# SCH_CableUndefinedMini_Rev2_2024-05-01.net
KiCad netlist of a schematic drawn in EasyEDA
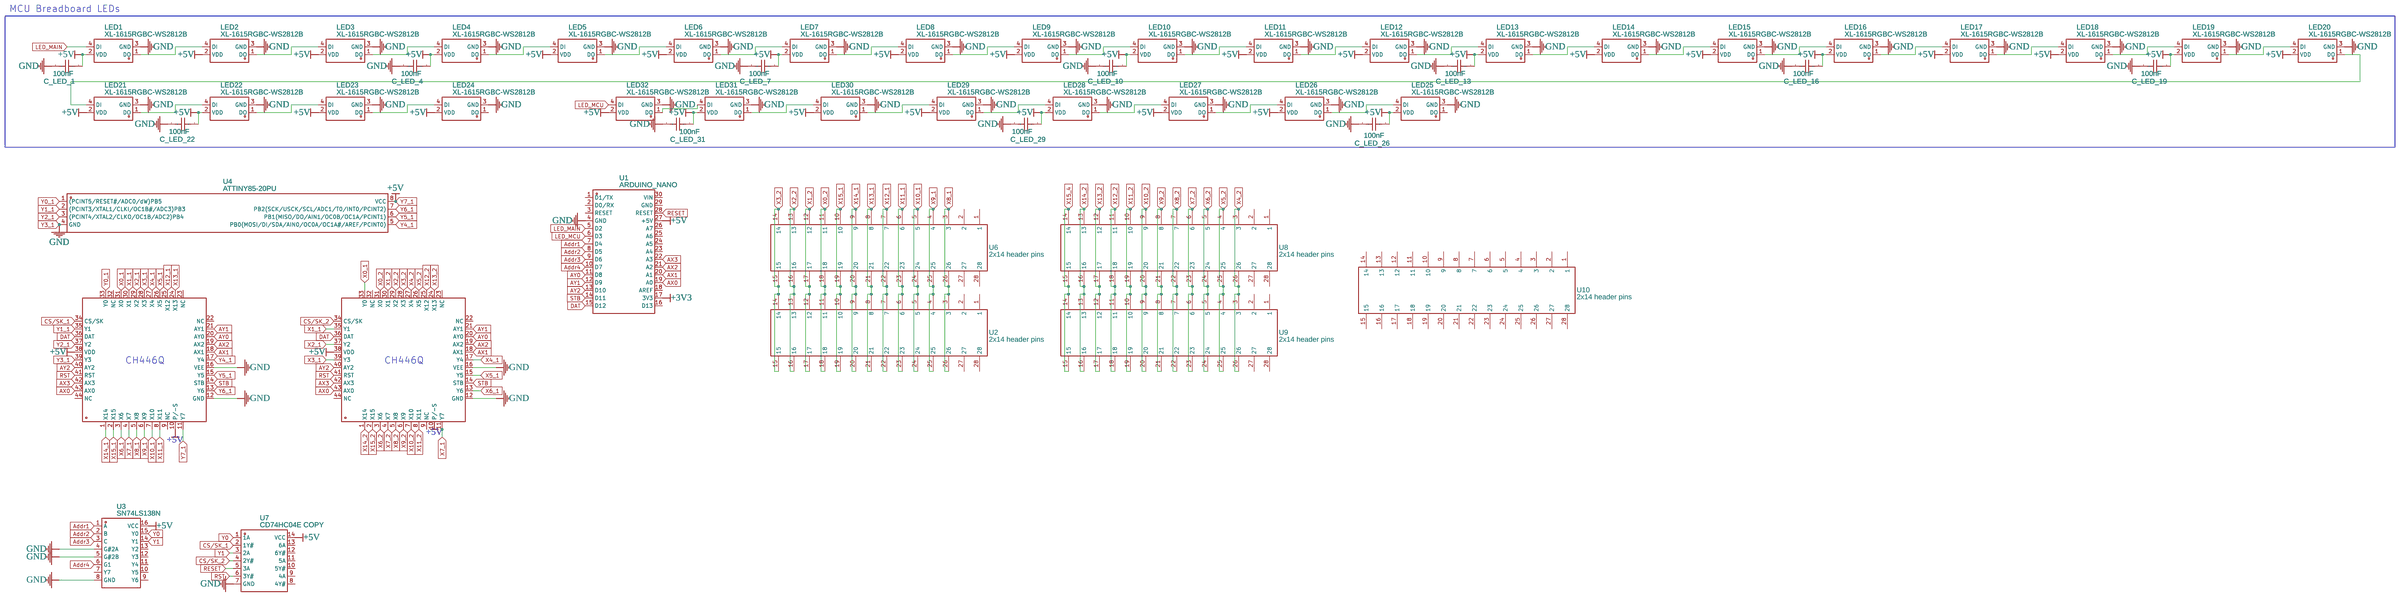
[diagram p0: schematic sheet]

(export (version "E")
  (design (tool "Eeschema 10.0.6"))
  (components
    (comp (ref "C_LED_1")
      (value "100nF")
      (fields (field (name "Manufacturer") "YAGEO(国巨)"))
      (libsource (lib "") (part "AC0402KRX7R9BB104"))
    )
    (comp (ref "C_LED_4")
      (value "100nF")
      (fields (field (name "Manufacturer") "YAGEO(国巨)"))
      (libsource (lib "") (part "AC0402KRX7R9BB104"))
    )
    (comp (ref "C_LED_7")
      (value "100nF")
      (fields (field (name "Manufacturer") "YAGEO(国巨)"))
      (libsource (lib "") (part "AC0402KRX7R9BB104"))
    )
    (comp (ref "C_LED_10")
      (value "100nF")
      (fields (field (name "Manufacturer") "YAGEO(国巨)"))
      (libsource (lib "") (part "AC0402KRX7R9BB104"))
    )
    (comp (ref "C_LED_13")
      (value "100nF")
      (fields (field (name "Manufacturer") "YAGEO(国巨)"))
      (libsource (lib "") (part "AC0402KRX7R9BB104"))
    )
    (comp (ref "C_LED_16")
      (value "100nF")
      (fields (field (name "Manufacturer") "YAGEO(国巨)"))
      (libsource (lib "") (part "AC0402KRX7R9BB104"))
    )
    (comp (ref "C_LED_19")
      (value "100nF")
      (fields (field (name "Manufacturer") "YAGEO(国巨)"))
      (libsource (lib "") (part "AC0402KRX7R9BB104"))
    )
    (comp (ref "C_LED_22")
      (value "100nF")
      (fields (field (name "Manufacturer") "YAGEO(国巨)"))
      (libsource (lib "") (part "AC0402KRX7R9BB104"))
    )
    (comp (ref "C_LED_26")
      (value "100nF")
      (fields (field (name "Manufacturer") "YAGEO(国巨)"))
      (libsource (lib "") (part "AC0402KRX7R9BB104"))
    )
    (comp (ref "C_LED_29")
      (value "100nF")
      (fields (field (name "Manufacturer") "YAGEO(国巨)"))
      (libsource (lib "") (part "AC0402KRX7R9BB104"))
    )
    (comp (ref "C_LED_31")
      (value "100nF")
      (fields (field (name "Manufacturer") "YAGEO(国巨)"))
      (libsource (lib "") (part "AC0402KRX7R9BB104"))
    )
    (comp (ref "LED1")
      (value "XL-1615RGBC-WS2812B")
      (fields (field (name "Manufacturer") "XINGLIGHT(成兴光)"))
      (libsource (lib "") (part "XL-1615RGBC-WS2812B"))
    )
    (comp (ref "LED2")
      (value "XL-1615RGBC-WS2812B")
      (fields (field (name "Manufacturer") "XINGLIGHT(成兴光)"))
      (libsource (lib "") (part "XL-1615RGBC-WS2812B"))
    )
    (comp (ref "LED3")
      (value "XL-1615RGBC-WS2812B")
      (fields (field (name "Manufacturer") "XINGLIGHT(成兴光)"))
      (libsource (lib "") (part "XL-1615RGBC-WS2812B"))
    )
    (comp (ref "LED4")
      (value "XL-1615RGBC-WS2812B")
      (fields (field (name "Manufacturer") "XINGLIGHT(成兴光)"))
      (libsource (lib "") (part "XL-1615RGBC-WS2812B"))
    )
    (comp (ref "LED5")
      (value "XL-1615RGBC-WS2812B")
      (fields (field (name "Manufacturer") "XINGLIGHT(成兴光)"))
      (libsource (lib "") (part "XL-1615RGBC-WS2812B"))
    )
    (comp (ref "LED6")
      (value "XL-1615RGBC-WS2812B")
      (fields (field (name "Manufacturer") "XINGLIGHT(成兴光)"))
      (libsource (lib "") (part "XL-1615RGBC-WS2812B"))
    )
    (comp (ref "LED7")
      (value "XL-1615RGBC-WS2812B")
      (fields (field (name "Manufacturer") "XINGLIGHT(成兴光)"))
      (libsource (lib "") (part "XL-1615RGBC-WS2812B"))
    )
    (comp (ref "LED8")
      (value "XL-1615RGBC-WS2812B")
      (fields (field (name "Manufacturer") "XINGLIGHT(成兴光)"))
      (libsource (lib "") (part "XL-1615RGBC-WS2812B"))
    )
    (comp (ref "LED9")
      (value "XL-1615RGBC-WS2812B")
      (fields (field (name "Manufacturer") "XINGLIGHT(成兴光)"))
      (libsource (lib "") (part "XL-1615RGBC-WS2812B"))
    )
    (comp (ref "LED10")
      (value "XL-1615RGBC-WS2812B")
      (fields (field (name "Manufacturer") "XINGLIGHT(成兴光)"))
      (libsource (lib "") (part "XL-1615RGBC-WS2812B"))
    )
    (comp (ref "LED11")
      (value "XL-1615RGBC-WS2812B")
      (fields (field (name "Manufacturer") "XINGLIGHT(成兴光)"))
      (libsource (lib "") (part "XL-1615RGBC-WS2812B"))
    )
    (comp (ref "LED12")
      (value "XL-1615RGBC-WS2812B")
      (fields (field (name "Manufacturer") "XINGLIGHT(成兴光)"))
      (libsource (lib "") (part "XL-1615RGBC-WS2812B"))
    )
    (comp (ref "LED13")
      (value "XL-1615RGBC-WS2812B")
      (fields (field (name "Manufacturer") "XINGLIGHT(成兴光)"))
      (libsource (lib "") (part "XL-1615RGBC-WS2812B"))
    )
    (comp (ref "LED14")
      (value "XL-1615RGBC-WS2812B")
      (fields (field (name "Manufacturer") "XINGLIGHT(成兴光)"))
      (libsource (lib "") (part "XL-1615RGBC-WS2812B"))
    )
    (comp (ref "LED15")
      (value "XL-1615RGBC-WS2812B")
      (fields (field (name "Manufacturer") "XINGLIGHT(成兴光)"))
      (libsource (lib "") (part "XL-1615RGBC-WS2812B"))
    )
    (comp (ref "LED16")
      (value "XL-1615RGBC-WS2812B")
      (fields (field (name "Manufacturer") "XINGLIGHT(成兴光)"))
      (libsource (lib "") (part "XL-1615RGBC-WS2812B"))
    )
    (comp (ref "LED17")
      (value "XL-1615RGBC-WS2812B")
      (fields (field (name "Manufacturer") "XINGLIGHT(成兴光)"))
      (libsource (lib "") (part "XL-1615RGBC-WS2812B"))
    )
    (comp (ref "LED18")
      (value "XL-1615RGBC-WS2812B")
      (fields (field (name "Manufacturer") "XINGLIGHT(成兴光)"))
      (libsource (lib "") (part "XL-1615RGBC-WS2812B"))
    )
    (comp (ref "LED19")
      (value "XL-1615RGBC-WS2812B")
      (fields (field (name "Manufacturer") "XINGLIGHT(成兴光)"))
      (libsource (lib "") (part "XL-1615RGBC-WS2812B"))
    )
    (comp (ref "LED20")
      (value "XL-1615RGBC-WS2812B")
      (fields (field (name "Manufacturer") "XINGLIGHT(成兴光)"))
      (libsource (lib "") (part "XL-1615RGBC-WS2812B"))
    )
    (comp (ref "LED21")
      (value "XL-1615RGBC-WS2812B")
      (fields (field (name "Manufacturer") "XINGLIGHT(成兴光)"))
      (libsource (lib "") (part "XL-1615RGBC-WS2812B"))
    )
    (comp (ref "LED22")
      (value "XL-1615RGBC-WS2812B")
      (fields (field (name "Manufacturer") "XINGLIGHT(成兴光)"))
      (libsource (lib "") (part "XL-1615RGBC-WS2812B"))
    )
    (comp (ref "LED23")
      (value "XL-1615RGBC-WS2812B")
      (fields (field (name "Manufacturer") "XINGLIGHT(成兴光)"))
      (libsource (lib "") (part "XL-1615RGBC-WS2812B"))
    )
    (comp (ref "LED24")
      (value "XL-1615RGBC-WS2812B")
      (fields (field (name "Manufacturer") "XINGLIGHT(成兴光)"))
      (libsource (lib "") (part "XL-1615RGBC-WS2812B"))
    )
    (comp (ref "LED25")
      (value "XL-1615RGBC-WS2812B")
      (fields (field (name "Manufacturer") "XINGLIGHT(成兴光)"))
      (libsource (lib "") (part "XL-1615RGBC-WS2812B"))
    )
    (comp (ref "LED26")
      (value "XL-1615RGBC-WS2812B")
      (fields (field (name "Manufacturer") "XINGLIGHT(成兴光)"))
      (libsource (lib "") (part "XL-1615RGBC-WS2812B"))
    )
    (comp (ref "LED27")
      (value "XL-1615RGBC-WS2812B")
      (fields (field (name "Manufacturer") "XINGLIGHT(成兴光)"))
      (libsource (lib "") (part "XL-1615RGBC-WS2812B"))
    )
    (comp (ref "LED28")
      (value "XL-1615RGBC-WS2812B")
      (fields (field (name "Manufacturer") "XINGLIGHT(成兴光)"))
      (libsource (lib "") (part "XL-1615RGBC-WS2812B"))
    )
    (comp (ref "LED29")
      (value "XL-1615RGBC-WS2812B")
      (fields (field (name "Manufacturer") "XINGLIGHT(成兴光)"))
      (libsource (lib "") (part "XL-1615RGBC-WS2812B"))
    )
    (comp (ref "LED30")
      (value "XL-1615RGBC-WS2812B")
      (fields (field (name "Manufacturer") "XINGLIGHT(成兴光)"))
      (libsource (lib "") (part "XL-1615RGBC-WS2812B"))
    )
    (comp (ref "LED31")
      (value "XL-1615RGBC-WS2812B")
      (fields (field (name "Manufacturer") "XINGLIGHT(成兴光)"))
      (libsource (lib "") (part "XL-1615RGBC-WS2812B"))
    )
    (comp (ref "LED32")
      (value "XL-1615RGBC-WS2812B")
      (fields (field (name "Manufacturer") "XINGLIGHT(成兴光)"))
      (libsource (lib "") (part "XL-1615RGBC-WS2812B"))
    )
    (comp (ref "M1")
      (value "CH446Q")
      (fields (field (name "Manufacturer") "WCH(南京沁恒)"))
      (libsource (lib "") (part "CH446Q"))
    )
    (comp (ref "M2")
      (value "CH446Q")
      (fields (field (name "Manufacturer") "WCH(南京沁恒)"))
      (libsource (lib "") (part "CH446Q"))
    )
    (comp (ref "U1") (value "ARDUINO_NANO") (libsource (lib "") (part "ARDUINO_NANO")))
    (comp (ref "U2") (value "2x14 header pins") (libsource (lib "") (part "2x14 header pins")))
    (comp (ref "U3")
      (value "SN74LS138N")
      (fields (field (name "Manufacturer") "TI(德州仪器)"))
      (libsource (lib "") (part "SN74LS138N"))
    )
    (comp (ref "U4")
      (value "ATTINY85-20PU")
      (fields (field (name "Manufacturer") "MICROCHIP(美国微芯)"))
      (libsource (lib "") (part "ATTINY85-20PU"))
    )
    (comp (ref "U6") (value "2x14 header pins") (libsource (lib "") (part "2x14 header pins")))
    (comp (ref "U7")
      (value "CD74HC04E COPY")
      (fields
        (field (name "Manufacturer Part") "CD74HC04E")
        (field (name "Manufacturer") "Texas Instruments")
      )
      (libsource (lib "") (part "CD74HC04E COPY"))
    )
    (comp (ref "U8") (value "2x14 header pins") (libsource (lib "") (part "2x14 header pins")))
    (comp (ref "U9") (value "2x14 header pins") (libsource (lib "") (part "2x14 header pins")))
    (comp (ref "U10") (value "2x14 header pins") (libsource (lib "") (part "2x14 header pins")))
  )
  (nets
    (net (code "1") (name "+3V3") (class "Default")
      (node (ref "U1") (pin "17") (pinfunction "3V3_17") (pintype "unspecified"))
    )
    (net (code "2") (name "AX0") (class "Default")
      (node (ref "M1") (pin "43") (pinfunction "AX0_43") (pintype "unspecified"))
      (node (ref "M2") (pin "43") (pinfunction "AX0_43") (pintype "unspecified"))
      (node (ref "U1") (pin "19") (pinfunction "A0_19") (pintype "unspecified"))
    )
    (net (code "3") (name "AX1") (class "Default")
      (node (ref "M1") (pin "18") (pinfunction "AX1_18") (pintype "unspecified"))
      (node (ref "M2") (pin "18") (pinfunction "AX1_18") (pintype "unspecified"))
      (node (ref "U1") (pin "20") (pinfunction "A1_20") (pintype "unspecified"))
    )
    (net (code "4") (name "AX2") (class "Default")
      (node (ref "M1") (pin "19") (pinfunction "AX2_19") (pintype "unspecified"))
      (node (ref "M2") (pin "19") (pinfunction "AX2_19") (pintype "unspecified"))
      (node (ref "U1") (pin "21") (pinfunction "A2_21") (pintype "unspecified"))
    )
    (net (code "5") (name "AX3") (class "Default")
      (node (ref "M1") (pin "42") (pinfunction "AX3_42") (pintype "unspecified"))
      (node (ref "M2") (pin "42") (pinfunction "AX3_42") (pintype "unspecified"))
      (node (ref "U1") (pin "22") (pinfunction "A3_22") (pintype "unspecified"))
    )
    (net (code "6") (name "AY0") (class "Default")
      (node (ref "M1") (pin "20") (pinfunction "AY0_20") (pintype "unspecified"))
      (node (ref "M2") (pin "20") (pinfunction "AY0_20") (pintype "unspecified"))
      (node (ref "U1") (pin "11") (pinfunction "D8_11") (pintype "unspecified"))
    )
    (net (code "7") (name "AY1") (class "Default")
      (node (ref "M1") (pin "21") (pinfunction "AY1_21") (pintype "unspecified"))
      (node (ref "M2") (pin "21") (pinfunction "AY1_21") (pintype "unspecified"))
      (node (ref "U1") (pin "12") (pinfunction "D9_12") (pintype "unspecified"))
    )
    (net (code "8") (name "AY2") (class "Default")
      (node (ref "M1") (pin "40") (pinfunction "AY2_40") (pintype "unspecified"))
      (node (ref "M2") (pin "40") (pinfunction "AY2_40") (pintype "unspecified"))
      (node (ref "U1") (pin "13") (pinfunction "D10_13") (pintype "unspecified"))
    )
    (net (code "9") (name "Addr1") (class "Default")
      (node (ref "U1") (pin "7") (pinfunction "D4_7") (pintype "unspecified"))
      (node (ref "U3") (pin "1") (pinfunction "A_1") (pintype "unspecified"))
    )
    (net (code "10") (name "Addr2") (class "Default")
      (node (ref "U1") (pin "8") (pinfunction "D5_8") (pintype "unspecified"))
      (node (ref "U3") (pin "2") (pinfunction "B_2") (pintype "unspecified"))
    )
    (net (code "11") (name "Addr3") (class "Default")
      (node (ref "U1") (pin "9") (pinfunction "D6_9") (pintype "unspecified"))
      (node (ref "U3") (pin "3") (pinfunction "C_3") (pintype "unspecified"))
    )
    (net (code "12") (name "Addr4") (class "Default")
      (node (ref "U1") (pin "10") (pinfunction "D7_10") (pintype "unspecified"))
      (node (ref "U3") (pin "6") (pinfunction "G1_6") (pintype "unspecified"))
    )
    (net (code "13") (name "CS{slash}SK_1") (class "Default")
      (node (ref "M1") (pin "34") (pinfunction "CS/SK_34") (pintype "unspecified"))
      (node (ref "U7") (pin "2") (pinfunction "1Y#_2") (pintype "unspecified"))
    )
    (net (code "14") (name "CS{slash}SK_2") (class "Default")
      (node (ref "M2") (pin "34") (pinfunction "CS/SK_34") (pintype "unspecified"))
      (node (ref "U7") (pin "4") (pinfunction "2Y#_4") (pintype "unspecified"))
    )
    (net (code "15") (name "DAT") (class "Default")
      (node (ref "M1") (pin "36") (pinfunction "DAT_36") (pintype "unspecified"))
      (node (ref "M2") (pin "36") (pinfunction "DAT_36") (pintype "unspecified"))
      (node (ref "U1") (pin "15") (pinfunction "D12_15") (pintype "unspecified"))
    )
    (net (code "16") (name "LED_MAIN") (class "Default")
      (node (ref "LED1") (pin "4") (pinfunction "DI_4") (pintype "unspecified"))
      (node (ref "U1") (pin "5") (pinfunction "D2_5") (pintype "unspecified"))
    )
    (net (code "17") (name "LED_MCU") (class "Default")
      (node (ref "LED32") (pin "4") (pinfunction "DI_4") (pintype "unspecified"))
      (node (ref "U1") (pin "6") (pinfunction "D3_6") (pintype "unspecified"))
    )
    (net (code "18") (name "Net-(LED1-DO)") (class "Default")
      (node (ref "LED1") (pin "1") (pinfunction "DO_1") (pintype "unspecified"))
      (node (ref "LED2") (pin "4") (pinfunction "DI_4") (pintype "unspecified"))
    )
    (net (code "19") (name "Net-(LED2-DO)") (class "Default")
      (node (ref "LED2") (pin "1") (pinfunction "DO_1") (pintype "unspecified"))
      (node (ref "LED3") (pin "4") (pinfunction "DI_4") (pintype "unspecified"))
    )
    (net (code "20") (name "Net-(LED3-DO)") (class "Default")
      (node (ref "LED3") (pin "1") (pinfunction "DO_1") (pintype "unspecified"))
      (node (ref "LED4") (pin "4") (pinfunction "DI_4") (pintype "unspecified"))
    )
    (net (code "21") (name "Net-(LED4-DO)") (class "Default")
      (node (ref "LED4") (pin "1") (pinfunction "DO_1") (pintype "unspecified"))
      (node (ref "LED5") (pin "4") (pinfunction "DI_4") (pintype "unspecified"))
    )
    (net (code "22") (name "Net-(LED5-DO)") (class "Default")
      (node (ref "LED5") (pin "1") (pinfunction "DO_1") (pintype "unspecified"))
      (node (ref "LED6") (pin "4") (pinfunction "DI_4") (pintype "unspecified"))
    )
    (net (code "23") (name "Net-(LED6-DO)") (class "Default")
      (node (ref "LED6") (pin "1") (pinfunction "DO_1") (pintype "unspecified"))
      (node (ref "LED7") (pin "4") (pinfunction "DI_4") (pintype "unspecified"))
    )
    (net (code "24") (name "Net-(LED7-DO)") (class "Default")
      (node (ref "LED7") (pin "1") (pinfunction "DO_1") (pintype "unspecified"))
      (node (ref "LED8") (pin "4") (pinfunction "DI_4") (pintype "unspecified"))
    )
    (net (code "25") (name "Net-(LED8-DO)") (class "Default")
      (node (ref "LED8") (pin "1") (pinfunction "DO_1") (pintype "unspecified"))
      (node (ref "LED9") (pin "4") (pinfunction "DI_4") (pintype "unspecified"))
    )
    (net (code "26") (name "Net-(LED10-DI)") (class "Default")
      (node (ref "LED10") (pin "4") (pinfunction "DI_4") (pintype "unspecified"))
      (node (ref "LED9") (pin "1") (pinfunction "DO_1") (pintype "unspecified"))
    )
    (net (code "27") (name "Net-(LED10-DO)") (class "Default")
      (node (ref "LED10") (pin "1") (pinfunction "DO_1") (pintype "unspecified"))
      (node (ref "LED11") (pin "4") (pinfunction "DI_4") (pintype "unspecified"))
    )
    (net (code "28") (name "Net-(LED11-DO)") (class "Default")
      (node (ref "LED11") (pin "1") (pinfunction "DO_1") (pintype "unspecified"))
      (node (ref "LED12") (pin "4") (pinfunction "DI_4") (pintype "unspecified"))
    )
    (net (code "29") (name "Net-(LED12-DO)") (class "Default")
      (node (ref "LED12") (pin "1") (pinfunction "DO_1") (pintype "unspecified"))
      (node (ref "LED13") (pin "4") (pinfunction "DI_4") (pintype "unspecified"))
    )
    (net (code "30") (name "Net-(LED13-DO)") (class "Default")
      (node (ref "LED13") (pin "1") (pinfunction "DO_1") (pintype "unspecified"))
      (node (ref "LED14") (pin "4") (pinfunction "DI_4") (pintype "unspecified"))
    )
    (net (code "31") (name "Net-(LED14-DO)") (class "Default")
      (node (ref "LED14") (pin "1") (pinfunction "DO_1") (pintype "unspecified"))
      (node (ref "LED15") (pin "4") (pinfunction "DI_4") (pintype "unspecified"))
    )
    (net (code "32") (name "Net-(LED15-DO)") (class "Default")
      (node (ref "LED15") (pin "1") (pinfunction "DO_1") (pintype "unspecified"))
      (node (ref "LED16") (pin "4") (pinfunction "DI_4") (pintype "unspecified"))
    )
    (net (code "33") (name "Net-(LED16-DO)") (class "Default")
      (node (ref "LED16") (pin "1") (pinfunction "DO_1") (pintype "unspecified"))
      (node (ref "LED17") (pin "4") (pinfunction "DI_4") (pintype "unspecified"))
    )
    (net (code "34") (name "Net-(LED17-DO)") (class "Default")
      (node (ref "LED17") (pin "1") (pinfunction "DO_1") (pintype "unspecified"))
      (node (ref "LED18") (pin "4") (pinfunction "DI_4") (pintype "unspecified"))
    )
    (net (code "35") (name "Net-(LED18-DO)") (class "Default")
      (node (ref "LED18") (pin "1") (pinfunction "DO_1") (pintype "unspecified"))
      (node (ref "LED19") (pin "4") (pinfunction "DI_4") (pintype "unspecified"))
    )
    (net (code "36") (name "Net-(LED19-DO)") (class "Default")
      (node (ref "LED19") (pin "1") (pinfunction "DO_1") (pintype "unspecified"))
      (node (ref "LED20") (pin "4") (pinfunction "DI_4") (pintype "unspecified"))
    )
    (net (code "37") (name "Net-(LED20-DO)") (class "Default")
      (node (ref "LED20") (pin "1") (pinfunction "DO_1") (pintype "unspecified"))
      (node (ref "LED21") (pin "4") (pinfunction "DI_4") (pintype "unspecified"))
    )
    (net (code "38") (name "Net-(LED21-DO)") (class "Default")
      (node (ref "LED21") (pin "1") (pinfunction "DO_1") (pintype "unspecified"))
      (node (ref "LED22") (pin "4") (pinfunction "DI_4") (pintype "unspecified"))
    )
    (net (code "39") (name "Net-(LED22-DO)") (class "Default")
      (node (ref "LED22") (pin "1") (pinfunction "DO_1") (pintype "unspecified"))
      (node (ref "LED23") (pin "4") (pinfunction "DI_4") (pintype "unspecified"))
    )
    (net (code "40") (name "Net-(LED23-DO)") (class "Default")
      (node (ref "LED23") (pin "1") (pinfunction "DO_1") (pintype "unspecified"))
      (node (ref "LED24") (pin "4") (pinfunction "DI_4") (pintype "unspecified"))
    )
    (net (code "41") (name "Net-(LED25-DI)") (class "Default")
      (node (ref "LED25") (pin "4") (pinfunction "DI_4") (pintype "unspecified"))
      (node (ref "LED26") (pin "1") (pinfunction "DO_1") (pintype "unspecified"))
    )
    (net (code "42") (name "Net-(LED26-DI)") (class "Default")
      (node (ref "LED26") (pin "4") (pinfunction "DI_4") (pintype "unspecified"))
      (node (ref "LED27") (pin "1") (pinfunction "DO_1") (pintype "unspecified"))
    )
    (net (code "43") (name "Net-(LED27-DI)") (class "Default")
      (node (ref "LED27") (pin "4") (pinfunction "DI_4") (pintype "unspecified"))
      (node (ref "LED28") (pin "1") (pinfunction "DO_1") (pintype "unspecified"))
    )
    (net (code "44") (name "Net-(LED28-DI)") (class "Default")
      (node (ref "LED28") (pin "4") (pinfunction "DI_4") (pintype "unspecified"))
      (node (ref "LED29") (pin "1") (pinfunction "DO_1") (pintype "unspecified"))
    )
    (net (code "45") (name "Net-(LED29-DI)") (class "Default")
      (node (ref "LED29") (pin "4") (pinfunction "DI_4") (pintype "unspecified"))
      (node (ref "LED30") (pin "1") (pinfunction "DO_1") (pintype "unspecified"))
    )
    (net (code "46") (name "Net-(LED30-DI)") (class "Default")
      (node (ref "LED30") (pin "4") (pinfunction "DI_4") (pintype "unspecified"))
      (node (ref "LED31") (pin "1") (pinfunction "DO_1") (pintype "unspecified"))
    )
    (net (code "47") (name "Net-(LED31-DI)") (class "Default")
      (node (ref "LED31") (pin "4") (pinfunction "DI_4") (pintype "unspecified"))
      (node (ref "LED32") (pin "1") (pinfunction "DO_1") (pintype "unspecified"))
    )
    (net (code "48") (name "RESET") (class "Default")
      (node (ref "U1") (pin "28") (pinfunction "RESET_28") (pintype "unspecified"))
      (node (ref "U7") (pin "5") (pinfunction "3A_5") (pintype "unspecified"))
    )
    (net (code "49") (name "RST") (class "Default")
      (node (ref "M1") (pin "41") (pinfunction "RST_41") (pintype "unspecified"))
      (node (ref "M2") (pin "41") (pinfunction "RST_41") (pintype "unspecified"))
      (node (ref "U7") (pin "6") (pinfunction "3Y#_6") (pintype "unspecified"))
    )
    (net (code "50") (name "STB") (class "Default")
      (node (ref "M1") (pin "14") (pinfunction "STB_14") (pintype "unspecified"))
      (node (ref "M2") (pin "14") (pinfunction "STB_14") (pintype "unspecified"))
      (node (ref "U1") (pin "14") (pinfunction "D11_14") (pintype "unspecified"))
    )
    (net (code "51") (name "X0_1") (class "Default")
      (node (ref "M1") (pin "31") (pinfunction "X0_31") (pintype "unspecified"))
      (node (ref "M2") (pin "33") (pinfunction "Y0_33") (pintype "unspecified"))
    )
    (net (code "52") (name "X0_2") (class "Default")
      (node (ref "M2") (pin "31") (pinfunction "X0_31") (pintype "unspecified"))
      (node (ref "U2") (pin "11") (pinfunction "11_11") (pintype "unspecified"))
      (node (ref "U2") (pin "18") (pinfunction "18_18") (pintype "unspecified"))
      (node (ref "U6") (pin "11") (pinfunction "11_11") (pintype "unspecified"))
      (node (ref "U6") (pin "18") (pinfunction "18_18") (pintype "unspecified"))
    )
    (net (code "53") (name "X1_1") (class "Default")
      (node (ref "M1") (pin "30") (pinfunction "X1_30") (pintype "unspecified"))
      (node (ref "M2") (pin "35") (pinfunction "Y1_35") (pintype "unspecified"))
    )
    (net (code "54") (name "X1_2") (class "Default")
      (node (ref "M2") (pin "30") (pinfunction "X1_30") (pintype "unspecified"))
      (node (ref "U2") (pin "12") (pinfunction "12_12") (pintype "unspecified"))
      (node (ref "U2") (pin "17") (pinfunction "17_17") (pintype "unspecified"))
      (node (ref "U6") (pin "12") (pinfunction "12_12") (pintype "unspecified"))
      (node (ref "U6") (pin "17") (pinfunction "17_17") (pintype "unspecified"))
    )
    (net (code "55") (name "X2_1") (class "Default")
      (node (ref "M1") (pin "29") (pinfunction "X2_29") (pintype "unspecified"))
      (node (ref "M2") (pin "37") (pinfunction "Y2_37") (pintype "unspecified"))
    )
    (net (code "56") (name "X2_2") (class "Default")
      (node (ref "M2") (pin "29") (pinfunction "X2_29") (pintype "unspecified"))
      (node (ref "U2") (pin "13") (pinfunction "13_13") (pintype "unspecified"))
      (node (ref "U2") (pin "16") (pinfunction "16_16") (pintype "unspecified"))
      (node (ref "U6") (pin "13") (pinfunction "13_13") (pintype "unspecified"))
      (node (ref "U6") (pin "16") (pinfunction "16_16") (pintype "unspecified"))
    )
    (net (code "57") (name "X3_1") (class "Default")
      (node (ref "M1") (pin "28") (pinfunction "X3_28") (pintype "unspecified"))
      (node (ref "M2") (pin "39") (pinfunction "Y3_39") (pintype "unspecified"))
    )
    (net (code "58") (name "X3_2") (class "Default")
      (node (ref "M2") (pin "28") (pinfunction "X3_28") (pintype "unspecified"))
      (node (ref "U2") (pin "14") (pinfunction "14_14") (pintype "unspecified"))
      (node (ref "U2") (pin "15") (pinfunction "15_15") (pintype "unspecified"))
      (node (ref "U6") (pin "14") (pinfunction "14_14") (pintype "unspecified"))
      (node (ref "U6") (pin "15") (pinfunction "15_15") (pintype "unspecified"))
    )
    (net (code "59") (name "X4_1") (class "Default")
      (node (ref "M1") (pin "27") (pinfunction "X4_27") (pintype "unspecified"))
      (node (ref "M2") (pin "17") (pinfunction "Y4_17") (pintype "unspecified"))
    )
    (net (code "60") (name "X4_2") (class "Default")
      (node (ref "M2") (pin "27") (pinfunction "X4_27") (pintype "unspecified"))
      (node (ref "U8") (pin "26") (pinfunction "26_26") (pintype "unspecified"))
      (node (ref "U8") (pin "3") (pinfunction "3_3") (pintype "unspecified"))
      (node (ref "U9") (pin "26") (pinfunction "26_26") (pintype "unspecified"))
      (node (ref "U9") (pin "3") (pinfunction "3_3") (pintype "unspecified"))
    )
    (net (code "61") (name "X5_1") (class "Default")
      (node (ref "M1") (pin "26") (pinfunction "X5_26") (pintype "unspecified"))
      (node (ref "M2") (pin "15") (pinfunction "Y5_15") (pintype "unspecified"))
    )
    (net (code "62") (name "X5_2") (class "Default")
      (node (ref "M2") (pin "26") (pinfunction "X5_26") (pintype "unspecified"))
      (node (ref "U8") (pin "25") (pinfunction "25_25") (pintype "unspecified"))
      (node (ref "U8") (pin "4") (pinfunction "4_4") (pintype "unspecified"))
      (node (ref "U9") (pin "25") (pinfunction "25_25") (pintype "unspecified"))
      (node (ref "U9") (pin "4") (pinfunction "4_4") (pintype "unspecified"))
    )
    (net (code "63") (name "X6_1") (class "Default")
      (node (ref "M1") (pin "3") (pinfunction "X6_3") (pintype "unspecified"))
      (node (ref "M2") (pin "13") (pinfunction "Y6_13") (pintype "unspecified"))
    )
    (net (code "64") (name "X6_2") (class "Default")
      (node (ref "M2") (pin "3") (pinfunction "X6_3") (pintype "unspecified"))
      (node (ref "U8") (pin "24") (pinfunction "24_24") (pintype "unspecified"))
      (node (ref "U8") (pin "5") (pinfunction "5_5") (pintype "unspecified"))
      (node (ref "U9") (pin "24") (pinfunction "24_24") (pintype "unspecified"))
      (node (ref "U9") (pin "5") (pinfunction "5_5") (pintype "unspecified"))
    )
    (net (code "65") (name "X7_1") (class "Default")
      (node (ref "M1") (pin "4") (pinfunction "X7_4") (pintype "unspecified"))
      (node (ref "M2") (pin "11") (pinfunction "Y7_11") (pintype "unspecified"))
    )
    (net (code "66") (name "X7_2") (class "Default")
      (node (ref "M2") (pin "4") (pinfunction "X7_4") (pintype "unspecified"))
      (node (ref "U8") (pin "23") (pinfunction "23_23") (pintype "unspecified"))
      (node (ref "U8") (pin "6") (pinfunction "6_6") (pintype "unspecified"))
      (node (ref "U9") (pin "23") (pinfunction "23_23") (pintype "unspecified"))
      (node (ref "U9") (pin "6") (pinfunction "6_6") (pintype "unspecified"))
    )
    (net (code "67") (name "X8_1") (class "Default")
      (node (ref "M1") (pin "5") (pinfunction "X8_5") (pintype "unspecified"))
      (node (ref "U2") (pin "26") (pinfunction "26_26") (pintype "unspecified"))
      (node (ref "U2") (pin "3") (pinfunction "3_3") (pintype "unspecified"))
      (node (ref "U6") (pin "26") (pinfunction "26_26") (pintype "unspecified"))
      (node (ref "U6") (pin "3") (pinfunction "3_3") (pintype "unspecified"))
    )
    (net (code "68") (name "X8_2") (class "Default")
      (node (ref "M2") (pin "5") (pinfunction "X8_5") (pintype "unspecified"))
      (node (ref "U8") (pin "22") (pinfunction "22_22") (pintype "unspecified"))
      (node (ref "U8") (pin "7") (pinfunction "7_7") (pintype "unspecified"))
      (node (ref "U9") (pin "22") (pinfunction "22_22") (pintype "unspecified"))
      (node (ref "U9") (pin "7") (pinfunction "7_7") (pintype "unspecified"))
    )
    (net (code "69") (name "X9_1") (class "Default")
      (node (ref "M1") (pin "6") (pinfunction "X9_6") (pintype "unspecified"))
      (node (ref "U2") (pin "25") (pinfunction "25_25") (pintype "unspecified"))
      (node (ref "U2") (pin "4") (pinfunction "4_4") (pintype "unspecified"))
      (node (ref "U6") (pin "25") (pinfunction "25_25") (pintype "unspecified"))
      (node (ref "U6") (pin "4") (pinfunction "4_4") (pintype "unspecified"))
    )
    (net (code "70") (name "X9_2") (class "Default")
      (node (ref "M2") (pin "6") (pinfunction "X9_6") (pintype "unspecified"))
      (node (ref "U8") (pin "21") (pinfunction "21_21") (pintype "unspecified"))
      (node (ref "U8") (pin "8") (pinfunction "8_8") (pintype "unspecified"))
      (node (ref "U9") (pin "21") (pinfunction "21_21") (pintype "unspecified"))
      (node (ref "U9") (pin "8") (pinfunction "8_8") (pintype "unspecified"))
    )
    (net (code "71") (name "X10_1") (class "Default")
      (node (ref "M1") (pin "7") (pinfunction "X10_7") (pintype "unspecified"))
      (node (ref "U2") (pin "24") (pinfunction "24_24") (pintype "unspecified"))
      (node (ref "U2") (pin "5") (pinfunction "5_5") (pintype "unspecified"))
      (node (ref "U6") (pin "24") (pinfunction "24_24") (pintype "unspecified"))
      (node (ref "U6") (pin "5") (pinfunction "5_5") (pintype "unspecified"))
    )
    (net (code "72") (name "X10_2") (class "Default")
      (node (ref "M2") (pin "7") (pinfunction "X10_7") (pintype "unspecified"))
      (node (ref "U8") (pin "20") (pinfunction "20_20") (pintype "unspecified"))
      (node (ref "U8") (pin "9") (pinfunction "9_9") (pintype "unspecified"))
      (node (ref "U9") (pin "20") (pinfunction "20_20") (pintype "unspecified"))
      (node (ref "U9") (pin "9") (pinfunction "9_9") (pintype "unspecified"))
    )
    (net (code "73") (name "X11_1") (class "Default")
      (node (ref "M1") (pin "8") (pinfunction "X11_8") (pintype "unspecified"))
      (node (ref "U2") (pin "23") (pinfunction "23_23") (pintype "unspecified"))
      (node (ref "U2") (pin "6") (pinfunction "6_6") (pintype "unspecified"))
      (node (ref "U6") (pin "23") (pinfunction "23_23") (pintype "unspecified"))
      (node (ref "U6") (pin "6") (pinfunction "6_6") (pintype "unspecified"))
    )
    (net (code "74") (name "X11_2") (class "Default")
      (node (ref "M2") (pin "8") (pinfunction "X11_8") (pintype "unspecified"))
      (node (ref "U8") (pin "10") (pinfunction "10_10") (pintype "unspecified"))
      (node (ref "U8") (pin "19") (pinfunction "19_19") (pintype "unspecified"))
      (node (ref "U9") (pin "10") (pinfunction "10_10") (pintype "unspecified"))
      (node (ref "U9") (pin "19") (pinfunction "19_19") (pintype "unspecified"))
    )
    (net (code "75") (name "X12_1") (class "Default")
      (node (ref "M1") (pin "25") (pinfunction "X12_25") (pintype "unspecified"))
      (node (ref "U2") (pin "22") (pinfunction "22_22") (pintype "unspecified"))
      (node (ref "U2") (pin "7") (pinfunction "7_7") (pintype "unspecified"))
      (node (ref "U6") (pin "22") (pinfunction "22_22") (pintype "unspecified"))
      (node (ref "U6") (pin "7") (pinfunction "7_7") (pintype "unspecified"))
    )
    (net (code "76") (name "X12_2") (class "Default")
      (node (ref "M2") (pin "25") (pinfunction "X12_25") (pintype "unspecified"))
      (node (ref "U8") (pin "11") (pinfunction "11_11") (pintype "unspecified"))
      (node (ref "U8") (pin "18") (pinfunction "18_18") (pintype "unspecified"))
      (node (ref "U9") (pin "11") (pinfunction "11_11") (pintype "unspecified"))
      (node (ref "U9") (pin "18") (pinfunction "18_18") (pintype "unspecified"))
    )
    (net (code "77") (name "X13_1") (class "Default")
      (node (ref "M1") (pin "24") (pinfunction "X13_24") (pintype "unspecified"))
      (node (ref "U2") (pin "21") (pinfunction "21_21") (pintype "unspecified"))
      (node (ref "U2") (pin "8") (pinfunction "8_8") (pintype "unspecified"))
      (node (ref "U6") (pin "21") (pinfunction "21_21") (pintype "unspecified"))
      (node (ref "U6") (pin "8") (pinfunction "8_8") (pintype "unspecified"))
    )
    (net (code "78") (name "X13_2") (class "Default")
      (node (ref "M2") (pin "24") (pinfunction "X13_24") (pintype "unspecified"))
      (node (ref "U8") (pin "12") (pinfunction "12_12") (pintype "unspecified"))
      (node (ref "U8") (pin "17") (pinfunction "17_17") (pintype "unspecified"))
      (node (ref "U9") (pin "12") (pinfunction "12_12") (pintype "unspecified"))
      (node (ref "U9") (pin "17") (pinfunction "17_17") (pintype "unspecified"))
    )
    (net (code "79") (name "X14_1") (class "Default")
      (node (ref "M1") (pin "1") (pinfunction "X14_1") (pintype "unspecified"))
      (node (ref "U2") (pin "20") (pinfunction "20_20") (pintype "unspecified"))
      (node (ref "U2") (pin "9") (pinfunction "9_9") (pintype "unspecified"))
      (node (ref "U6") (pin "20") (pinfunction "20_20") (pintype "unspecified"))
      (node (ref "U6") (pin "9") (pinfunction "9_9") (pintype "unspecified"))
    )
    (net (code "80") (name "X14_2") (class "Default")
      (node (ref "M2") (pin "1") (pinfunction "X14_1") (pintype "unspecified"))
      (node (ref "U8") (pin "13") (pinfunction "13_13") (pintype "unspecified"))
      (node (ref "U8") (pin "16") (pinfunction "16_16") (pintype "unspecified"))
      (node (ref "U9") (pin "13") (pinfunction "13_13") (pintype "unspecified"))
      (node (ref "U9") (pin "16") (pinfunction "16_16") (pintype "unspecified"))
    )
    (net (code "81") (name "X15_1") (class "Default")
      (node (ref "M1") (pin "2") (pinfunction "X15_2") (pintype "unspecified"))
      (node (ref "U2") (pin "10") (pinfunction "10_10") (pintype "unspecified"))
      (node (ref "U2") (pin "19") (pinfunction "19_19") (pintype "unspecified"))
      (node (ref "U6") (pin "10") (pinfunction "10_10") (pintype "unspecified"))
      (node (ref "U6") (pin "19") (pinfunction "19_19") (pintype "unspecified"))
    )
    (net (code "82") (name "X15_2") (class "Default")
      (node (ref "M2") (pin "2") (pinfunction "X15_2") (pintype "unspecified"))
    )
    (net (code "83") (name "X15_4") (class "Default")
      (node (ref "U8") (pin "14") (pinfunction "14_14") (pintype "unspecified"))
      (node (ref "U8") (pin "15") (pinfunction "15_15") (pintype "unspecified"))
      (node (ref "U9") (pin "14") (pinfunction "14_14") (pintype "unspecified"))
      (node (ref "U9") (pin "15") (pinfunction "15_15") (pintype "unspecified"))
    )
    (net (code "84") (name "Y0") (class "Default")
      (node (ref "U3") (pin "15") (pinfunction "Y0_15") (pintype "unspecified"))
      (node (ref "U7") (pin "1") (pinfunction "1A_1") (pintype "unspecified"))
    )
    (net (code "85") (name "Y0_1") (class "Default")
      (node (ref "M1") (pin "33") (pinfunction "Y0_33") (pintype "unspecified"))
      (node (ref "U4") (pin "1") (pinfunction "(PCINT5/RESET#/ADC0/dW)PB5_1") (pintype "unspecified"))
    )
    (net (code "86") (name "Y1") (class "Default")
      (node (ref "U3") (pin "14") (pinfunction "Y1_14") (pintype "unspecified"))
      (node (ref "U7") (pin "3") (pinfunction "2A_3") (pintype "unspecified"))
    )
    (net (code "87") (name "Y1_1") (class "Default")
      (node (ref "M1") (pin "35") (pinfunction "Y1_35") (pintype "unspecified"))
      (node (ref "U4") (pin "2") (pinfunction "(PCINT3/XTAL1/CLKI/OC1B#/ADC3)PB3_2") (pintype "unspecified"))
    )
    (net (code "88") (name "Y2_1") (class "Default")
      (node (ref "M1") (pin "37") (pinfunction "Y2_37") (pintype "unspecified"))
      (node (ref "U4") (pin "3") (pinfunction "(PCINT4/XTAL2/CLKO/OC1B/ADC2)PB4_3") (pintype "unspecified"))
    )
    (net (code "89") (name "Y3_1") (class "Default")
      (node (ref "C_LED_1") (pin "2") (pinfunction "2_2") (pintype "unspecified"))
      (node (ref "C_LED_10") (pin "2") (pinfunction "2_2") (pintype "unspecified"))
      (node (ref "C_LED_13") (pin "2") (pinfunction "2_2") (pintype "unspecified"))
      (node (ref "C_LED_16") (pin "2") (pinfunction "2_2") (pintype "unspecified"))
      (node (ref "C_LED_19") (pin "2") (pinfunction "2_2") (pintype "unspecified"))
      (node (ref "C_LED_22") (pin "2") (pinfunction "2_2") (pintype "unspecified"))
      (node (ref "C_LED_26") (pin "2") (pinfunction "2_2") (pintype "unspecified"))
      (node (ref "C_LED_29") (pin "2") (pinfunction "2_2") (pintype "unspecified"))
      (node (ref "C_LED_31") (pin "2") (pinfunction "2_2") (pintype "unspecified"))
      (node (ref "C_LED_4") (pin "2") (pinfunction "2_2") (pintype "unspecified"))
      (node (ref "C_LED_7") (pin "2") (pinfunction "2_2") (pintype "unspecified"))
      (node (ref "LED1") (pin "3") (pinfunction "GND_3") (pintype "unspecified"))
      (node (ref "LED10") (pin "3") (pinfunction "GND_3") (pintype "unspecified"))
      (node (ref "LED11") (pin "3") (pinfunction "GND_3") (pintype "unspecified"))
      (node (ref "LED12") (pin "3") (pinfunction "GND_3") (pintype "unspecified"))
      (node (ref "LED13") (pin "3") (pinfunction "GND_3") (pintype "unspecified"))
      (node (ref "LED14") (pin "3") (pinfunction "GND_3") (pintype "unspecified"))
      (node (ref "LED15") (pin "3") (pinfunction "GND_3") (pintype "unspecified"))
      (node (ref "LED16") (pin "3") (pinfunction "GND_3") (pintype "unspecified"))
      (node (ref "LED17") (pin "3") (pinfunction "GND_3") (pintype "unspecified"))
      (node (ref "LED18") (pin "3") (pinfunction "GND_3") (pintype "unspecified"))
      (node (ref "LED19") (pin "3") (pinfunction "GND_3") (pintype "unspecified"))
      (node (ref "LED2") (pin "3") (pinfunction "GND_3") (pintype "unspecified"))
      (node (ref "LED20") (pin "3") (pinfunction "GND_3") (pintype "unspecified"))
      (node (ref "LED21") (pin "3") (pinfunction "GND_3") (pintype "unspecified"))
      (node (ref "LED22") (pin "3") (pinfunction "GND_3") (pintype "unspecified"))
      (node (ref "LED23") (pin "3") (pinfunction "GND_3") (pintype "unspecified"))
      (node (ref "LED24") (pin "3") (pinfunction "GND_3") (pintype "unspecified"))
      (node (ref "LED25") (pin "3") (pinfunction "GND_3") (pintype "unspecified"))
      (node (ref "LED26") (pin "3") (pinfunction "GND_3") (pintype "unspecified"))
      (node (ref "LED27") (pin "3") (pinfunction "GND_3") (pintype "unspecified"))
      (node (ref "LED28") (pin "3") (pinfunction "GND_3") (pintype "unspecified"))
      (node (ref "LED29") (pin "3") (pinfunction "GND_3") (pintype "unspecified"))
      (node (ref "LED3") (pin "3") (pinfunction "GND_3") (pintype "unspecified"))
      (node (ref "LED30") (pin "3") (pinfunction "GND_3") (pintype "unspecified"))
      (node (ref "LED31") (pin "3") (pinfunction "GND_3") (pintype "unspecified"))
      (node (ref "LED32") (pin "3") (pinfunction "GND_3") (pintype "unspecified"))
      (node (ref "LED4") (pin "3") (pinfunction "GND_3") (pintype "unspecified"))
      (node (ref "LED5") (pin "3") (pinfunction "GND_3") (pintype "unspecified"))
      (node (ref "LED6") (pin "3") (pinfunction "GND_3") (pintype "unspecified"))
      (node (ref "LED7") (pin "3") (pinfunction "GND_3") (pintype "unspecified"))
      (node (ref "LED8") (pin "3") (pinfunction "GND_3") (pintype "unspecified"))
      (node (ref "LED9") (pin "3") (pinfunction "GND_3") (pintype "unspecified"))
      (node (ref "M1") (pin "12") (pinfunction "GND_12") (pintype "unspecified"))
      (node (ref "M1") (pin "16") (pinfunction "VEE_16") (pintype "unspecified"))
      (node (ref "M1") (pin "39") (pinfunction "Y3_39") (pintype "unspecified"))
      (node (ref "M2") (pin "12") (pinfunction "GND_12") (pintype "unspecified"))
      (node (ref "M2") (pin "16") (pinfunction "VEE_16") (pintype "unspecified"))
      (node (ref "U1") (pin "4") (pinfunction "GND_4") (pintype "unspecified"))
      (node (ref "U3") (pin "4") (pinfunction "G#2A_4") (pintype "unspecified"))
      (node (ref "U3") (pin "5") (pinfunction "G#2B_5") (pintype "unspecified"))
      (node (ref "U3") (pin "8") (pinfunction "GND_8") (pintype "unspecified"))
      (node (ref "U4") (pin "4") (pinfunction "GND_4") (pintype "unspecified"))
      (node (ref "U7") (pin "7") (pinfunction "GND_7") (pintype "unspecified"))
    )
    (net (code "90") (name "Y4_1") (class "Default")
      (node (ref "M1") (pin "17") (pinfunction "Y4_17") (pintype "unspecified"))
      (node (ref "U4") (pin "5") (pinfunction "PB0(MOSI/DI/SDA/AIN0/OC0A/OC1A#/AREF/PCINT0)_5") (pintype "unspecified"))
    )
    (net (code "91") (name "Y5_1") (class "Default")
      (node (ref "M1") (pin "15") (pinfunction "Y5_15") (pintype "unspecified"))
      (node (ref "U4") (pin "6") (pinfunction "PB1(MISO/DO/AIN1/OC0B/OC1A/PCINT1)_6") (pintype "unspecified"))
    )
    (net (code "92") (name "Y6_1") (class "Default")
      (node (ref "M1") (pin "13") (pinfunction "Y6_13") (pintype "unspecified"))
      (node (ref "U4") (pin "7") (pinfunction "PB2(SCK/USCK/SCL/ADC1/T0/INT0/PCINT2)_7") (pintype "unspecified"))
    )
    (net (code "93") (name "Y7_1") (class "Default")
      (node (ref "C_LED_1") (pin "1") (pinfunction "1_1") (pintype "unspecified"))
      (node (ref "C_LED_10") (pin "1") (pinfunction "1_1") (pintype "unspecified"))
      (node (ref "C_LED_13") (pin "1") (pinfunction "1_1") (pintype "unspecified"))
      (node (ref "C_LED_16") (pin "1") (pinfunction "1_1") (pintype "unspecified"))
      (node (ref "C_LED_19") (pin "1") (pinfunction "1_1") (pintype "unspecified"))
      (node (ref "C_LED_22") (pin "1") (pinfunction "1_1") (pintype "unspecified"))
      (node (ref "C_LED_26") (pin "1") (pinfunction "1_1") (pintype "unspecified"))
      (node (ref "C_LED_29") (pin "1") (pinfunction "1_1") (pintype "unspecified"))
      (node (ref "C_LED_31") (pin "1") (pinfunction "1_1") (pintype "unspecified"))
      (node (ref "C_LED_4") (pin "1") (pinfunction "1_1") (pintype "unspecified"))
      (node (ref "C_LED_7") (pin "1") (pinfunction "1_1") (pintype "unspecified"))
      (node (ref "LED1") (pin "2") (pinfunction "VDD_2") (pintype "unspecified"))
      (node (ref "LED10") (pin "2") (pinfunction "VDD_2") (pintype "unspecified"))
      (node (ref "LED11") (pin "2") (pinfunction "VDD_2") (pintype "unspecified"))
      (node (ref "LED12") (pin "2") (pinfunction "VDD_2") (pintype "unspecified"))
      (node (ref "LED13") (pin "2") (pinfunction "VDD_2") (pintype "unspecified"))
      (node (ref "LED14") (pin "2") (pinfunction "VDD_2") (pintype "unspecified"))
      (node (ref "LED15") (pin "2") (pinfunction "VDD_2") (pintype "unspecified"))
      (node (ref "LED16") (pin "2") (pinfunction "VDD_2") (pintype "unspecified"))
      (node (ref "LED17") (pin "2") (pinfunction "VDD_2") (pintype "unspecified"))
      (node (ref "LED18") (pin "2") (pinfunction "VDD_2") (pintype "unspecified"))
      (node (ref "LED19") (pin "2") (pinfunction "VDD_2") (pintype "unspecified"))
      (node (ref "LED2") (pin "2") (pinfunction "VDD_2") (pintype "unspecified"))
      (node (ref "LED20") (pin "2") (pinfunction "VDD_2") (pintype "unspecified"))
      (node (ref "LED21") (pin "2") (pinfunction "VDD_2") (pintype "unspecified"))
      (node (ref "LED22") (pin "2") (pinfunction "VDD_2") (pintype "unspecified"))
      (node (ref "LED23") (pin "2") (pinfunction "VDD_2") (pintype "unspecified"))
      (node (ref "LED24") (pin "2") (pinfunction "VDD_2") (pintype "unspecified"))
      (node (ref "LED25") (pin "2") (pinfunction "VDD_2") (pintype "unspecified"))
      (node (ref "LED26") (pin "2") (pinfunction "VDD_2") (pintype "unspecified"))
      (node (ref "LED27") (pin "2") (pinfunction "VDD_2") (pintype "unspecified"))
      (node (ref "LED28") (pin "2") (pinfunction "VDD_2") (pintype "unspecified"))
      (node (ref "LED29") (pin "2") (pinfunction "VDD_2") (pintype "unspecified"))
      (node (ref "LED3") (pin "2") (pinfunction "VDD_2") (pintype "unspecified"))
      (node (ref "LED30") (pin "2") (pinfunction "VDD_2") (pintype "unspecified"))
      (node (ref "LED31") (pin "2") (pinfunction "VDD_2") (pintype "unspecified"))
      (node (ref "LED32") (pin "2") (pinfunction "VDD_2") (pintype "unspecified"))
      (node (ref "LED4") (pin "2") (pinfunction "VDD_2") (pintype "unspecified"))
      (node (ref "LED5") (pin "2") (pinfunction "VDD_2") (pintype "unspecified"))
      (node (ref "LED6") (pin "2") (pinfunction "VDD_2") (pintype "unspecified"))
      (node (ref "LED7") (pin "2") (pinfunction "VDD_2") (pintype "unspecified"))
      (node (ref "LED8") (pin "2") (pinfunction "VDD_2") (pintype "unspecified"))
      (node (ref "LED9") (pin "2") (pinfunction "VDD_2") (pintype "unspecified"))
      (node (ref "M1") (pin "10") (pinfunction "P/-S_10") (pintype "unspecified"))
      (node (ref "M1") (pin "11") (pinfunction "Y7_11") (pintype "unspecified"))
      (node (ref "M1") (pin "38") (pinfunction "VDD_38") (pintype "unspecified"))
      (node (ref "M2") (pin "10") (pinfunction "P/-S_10") (pintype "unspecified"))
      (node (ref "M2") (pin "38") (pinfunction "VDD_38") (pintype "unspecified"))
      (node (ref "U1") (pin "27") (pinfunction "+5V_27") (pintype "unspecified"))
      (node (ref "U3") (pin "16") (pinfunction "VCC_16") (pintype "unspecified"))
      (node (ref "U4") (pin "8") (pinfunction "VCC_8") (pintype "unspecified"))
      (node (ref "U7") (pin "14") (pinfunction "VCC_14") (pintype "unspecified"))
    )
    (net (code "94") (name "unconnected-(LED24-DO-Pad1)") (class "Default")
      (node (ref "LED24") (pin "1") (pinfunction "DO_1") (pintype "unspecified"))
    )
    (net (code "95") (name "unconnected-(LED25-DO-Pad1)") (class "Default")
      (node (ref "LED25") (pin "1") (pinfunction "DO_1") (pintype "unspecified"))
    )
    (net (code "96") (name "unconnected-(M1-NC-Pad9)") (class "Default")
      (node (ref "M1") (pin "9") (pinfunction "NC_9") (pintype "unspecified"))
    )
    (net (code "97") (name "unconnected-(M1-NC-Pad22)") (class "Default")
      (node (ref "M1") (pin "22") (pinfunction "NC_22") (pintype "unspecified"))
    )
    (net (code "98") (name "unconnected-(M1-NC-Pad23)") (class "Default")
      (node (ref "M1") (pin "23") (pinfunction "NC_23") (pintype "unspecified"))
    )
    (net (code "99") (name "unconnected-(M1-NC-Pad32)") (class "Default")
      (node (ref "M1") (pin "32") (pinfunction "NC_32") (pintype "unspecified"))
    )
    (net (code "100") (name "unconnected-(M1-NC-Pad44)") (class "Default")
      (node (ref "M1") (pin "44") (pinfunction "NC_44") (pintype "unspecified"))
    )
    (net (code "101") (name "unconnected-(M2-NC-Pad9)") (class "Default")
      (node (ref "M2") (pin "9") (pinfunction "NC_9") (pintype "unspecified"))
    )
    (net (code "102") (name "unconnected-(M2-NC-Pad22)") (class "Default")
      (node (ref "M2") (pin "22") (pinfunction "NC_22") (pintype "unspecified"))
    )
    (net (code "103") (name "unconnected-(M2-NC-Pad23)") (class "Default")
      (node (ref "M2") (pin "23") (pinfunction "NC_23") (pintype "unspecified"))
    )
    (net (code "104") (name "unconnected-(M2-NC-Pad32)") (class "Default")
      (node (ref "M2") (pin "32") (pinfunction "NC_32") (pintype "unspecified"))
    )
    (net (code "105") (name "unconnected-(M2-NC-Pad44)") (class "Default")
      (node (ref "M2") (pin "44") (pinfunction "NC_44") (pintype "unspecified"))
    )
    (net (code "106") (name "unconnected-(U1-A4-Pad23)") (class "Default")
      (node (ref "U1") (pin "23") (pinfunction "A4_23") (pintype "unspecified"))
    )
    (net (code "107") (name "unconnected-(U1-A5-Pad24)") (class "Default")
      (node (ref "U1") (pin "24") (pinfunction "A5_24") (pintype "unspecified"))
    )
    (net (code "108") (name "unconnected-(U1-A6-Pad25)") (class "Default")
      (node (ref "U1") (pin "25") (pinfunction "A6_25") (pintype "unspecified"))
    )
    (net (code "109") (name "unconnected-(U1-A7-Pad26)") (class "Default")
      (node (ref "U1") (pin "26") (pinfunction "A7_26") (pintype "unspecified"))
    )
    (net (code "110") (name "unconnected-(U1-AREF-Pad18)") (class "Default")
      (node (ref "U1") (pin "18") (pinfunction "AREF_18") (pintype "unspecified"))
    )
    (net (code "111") (name "unconnected-(U1-D0{slash}RX-Pad2)") (class "Default")
      (node (ref "U1") (pin "2") (pinfunction "D0/RX_2") (pintype "unspecified"))
    )
    (net (code "112") (name "unconnected-(U1-D1{slash}TX-Pad1)") (class "Default")
      (node (ref "U1") (pin "1") (pinfunction "D1/TX_1") (pintype "unspecified"))
    )
    (net (code "113") (name "unconnected-(U1-D13-Pad16)") (class "Default")
      (node (ref "U1") (pin "16") (pinfunction "D13_16") (pintype "unspecified"))
    )
    (net (code "114") (name "unconnected-(U1-GND-Pad29)") (class "Default")
      (node (ref "U1") (pin "29") (pinfunction "GND_29") (pintype "unspecified"))
    )
    (net (code "115") (name "unconnected-(U1-RESET-Pad3)") (class "Default")
      (node (ref "U1") (pin "3") (pinfunction "RESET_3") (pintype "unspecified"))
    )
    (net (code "116") (name "unconnected-(U1-VIN-Pad30)") (class "Default")
      (node (ref "U1") (pin "30") (pinfunction "VIN_30") (pintype "unspecified"))
    )
    (net (code "117") (name "unconnected-(U2-Pad1)") (class "Default")
      (node (ref "U2") (pin "1") (pinfunction "1_1") (pintype "unspecified"))
    )
    (net (code "118") (name "unconnected-(U2-Pad2)") (class "Default")
      (node (ref "U2") (pin "2") (pinfunction "2_2") (pintype "unspecified"))
    )
    (net (code "119") (name "unconnected-(U2-Pad27)") (class "Default")
      (node (ref "U2") (pin "27") (pinfunction "27_27") (pintype "unspecified"))
    )
    (net (code "120") (name "unconnected-(U2-Pad28)") (class "Default")
      (node (ref "U2") (pin "28") (pinfunction "28_28") (pintype "unspecified"))
    )
    (net (code "121") (name "unconnected-(U3-Y2-Pad13)") (class "Default")
      (node (ref "U3") (pin "13") (pinfunction "Y2_13") (pintype "unspecified"))
    )
    (net (code "122") (name "unconnected-(U3-Y3-Pad12)") (class "Default")
      (node (ref "U3") (pin "12") (pinfunction "Y3_12") (pintype "unspecified"))
    )
    (net (code "123") (name "unconnected-(U3-Y4-Pad11)") (class "Default")
      (node (ref "U3") (pin "11") (pinfunction "Y4_11") (pintype "unspecified"))
    )
    (net (code "124") (name "unconnected-(U3-Y5-Pad10)") (class "Default")
      (node (ref "U3") (pin "10") (pinfunction "Y5_10") (pintype "unspecified"))
    )
    (net (code "125") (name "unconnected-(U3-Y6-Pad9)") (class "Default")
      (node (ref "U3") (pin "9") (pinfunction "Y6_9") (pintype "unspecified"))
    )
    (net (code "126") (name "unconnected-(U3-Y7-Pad7)") (class "Default")
      (node (ref "U3") (pin "7") (pinfunction "Y7_7") (pintype "unspecified"))
    )
    (net (code "127") (name "unconnected-(U6-Pad1)") (class "Default")
      (node (ref "U6") (pin "1") (pinfunction "1_1") (pintype "unspecified"))
    )
    (net (code "128") (name "unconnected-(U6-Pad2)") (class "Default")
      (node (ref "U6") (pin "2") (pinfunction "2_2") (pintype "unspecified"))
    )
    (net (code "129") (name "unconnected-(U6-Pad27)") (class "Default")
      (node (ref "U6") (pin "27") (pinfunction "27_27") (pintype "unspecified"))
    )
    (net (code "130") (name "unconnected-(U6-Pad28)") (class "Default")
      (node (ref "U6") (pin "28") (pinfunction "28_28") (pintype "unspecified"))
    )
    (net (code "131") (name "unconnected-(U7-4A-Pad9)") (class "Default")
      (node (ref "U7") (pin "9") (pinfunction "4A_9") (pintype "unspecified"))
    )
    (net (code "132") (name "unconnected-(U7-4Y#-Pad8)") (class "Default")
      (node (ref "U7") (pin "8") (pinfunction "4Y#_8") (pintype "unspecified"))
    )
    (net (code "133") (name "unconnected-(U7-5A-Pad11)") (class "Default")
      (node (ref "U7") (pin "11") (pinfunction "5A_11") (pintype "unspecified"))
    )
    (net (code "134") (name "unconnected-(U7-5Y#-Pad10)") (class "Default")
      (node (ref "U7") (pin "10") (pinfunction "5Y#_10") (pintype "unspecified"))
    )
    (net (code "135") (name "unconnected-(U7-6A-Pad13)") (class "Default")
      (node (ref "U7") (pin "13") (pinfunction "6A_13") (pintype "unspecified"))
    )
    (net (code "136") (name "unconnected-(U7-6Y#-Pad12)") (class "Default")
      (node (ref "U7") (pin "12") (pinfunction "6Y#_12") (pintype "unspecified"))
    )
    (net (code "137") (name "unconnected-(U8-Pad1)") (class "Default")
      (node (ref "U8") (pin "1") (pinfunction "1_1") (pintype "unspecified"))
    )
    (net (code "138") (name "unconnected-(U8-Pad2)") (class "Default")
      (node (ref "U8") (pin "2") (pinfunction "2_2") (pintype "unspecified"))
    )
    (net (code "139") (name "unconnected-(U8-Pad27)") (class "Default")
      (node (ref "U8") (pin "27") (pinfunction "27_27") (pintype "unspecified"))
    )
    (net (code "140") (name "unconnected-(U8-Pad28)") (class "Default")
      (node (ref "U8") (pin "28") (pinfunction "28_28") (pintype "unspecified"))
    )
    (net (code "141") (name "unconnected-(U9-Pad1)") (class "Default")
      (node (ref "U9") (pin "1") (pinfunction "1_1") (pintype "unspecified"))
    )
    (net (code "142") (name "unconnected-(U9-Pad2)") (class "Default")
      (node (ref "U9") (pin "2") (pinfunction "2_2") (pintype "unspecified"))
    )
    (net (code "143") (name "unconnected-(U9-Pad27)") (class "Default")
      (node (ref "U9") (pin "27") (pinfunction "27_27") (pintype "unspecified"))
    )
    (net (code "144") (name "unconnected-(U9-Pad28)") (class "Default")
      (node (ref "U9") (pin "28") (pinfunction "28_28") (pintype "unspecified"))
    )
    (net (code "145") (name "unconnected-(U10-Pad1)") (class "Default")
      (node (ref "U10") (pin "1") (pinfunction "1_1") (pintype "unspecified"))
    )
    (net (code "146") (name "unconnected-(U10-Pad2)") (class "Default")
      (node (ref "U10") (pin "2") (pinfunction "2_2") (pintype "unspecified"))
    )
    (net (code "147") (name "unconnected-(U10-Pad3)") (class "Default")
      (node (ref "U10") (pin "3") (pinfunction "3_3") (pintype "unspecified"))
    )
    (net (code "148") (name "unconnected-(U10-Pad4)") (class "Default")
      (node (ref "U10") (pin "4") (pinfunction "4_4") (pintype "unspecified"))
    )
    (net (code "149") (name "unconnected-(U10-Pad5)") (class "Default")
      (node (ref "U10") (pin "5") (pinfunction "5_5") (pintype "unspecified"))
    )
    (net (code "150") (name "unconnected-(U10-Pad6)") (class "Default")
      (node (ref "U10") (pin "6") (pinfunction "6_6") (pintype "unspecified"))
    )
    (net (code "151") (name "unconnected-(U10-Pad7)") (class "Default")
      (node (ref "U10") (pin "7") (pinfunction "7_7") (pintype "unspecified"))
    )
    (net (code "152") (name "unconnected-(U10-Pad8)") (class "Default")
      (node (ref "U10") (pin "8") (pinfunction "8_8") (pintype "unspecified"))
    )
    (net (code "153") (name "unconnected-(U10-Pad9)") (class "Default")
      (node (ref "U10") (pin "9") (pinfunction "9_9") (pintype "unspecified"))
    )
    (net (code "154") (name "unconnected-(U10-Pad10)") (class "Default")
      (node (ref "U10") (pin "10") (pinfunction "10_10") (pintype "unspecified"))
    )
    (net (code "155") (name "unconnected-(U10-Pad11)") (class "Default")
      (node (ref "U10") (pin "11") (pinfunction "11_11") (pintype "unspecified"))
    )
    (net (code "156") (name "unconnected-(U10-Pad12)") (class "Default")
      (node (ref "U10") (pin "12") (pinfunction "12_12") (pintype "unspecified"))
    )
    (net (code "157") (name "unconnected-(U10-Pad13)") (class "Default")
      (node (ref "U10") (pin "13") (pinfunction "13_13") (pintype "unspecified"))
    )
    (net (code "158") (name "unconnected-(U10-Pad14)") (class "Default")
      (node (ref "U10") (pin "14") (pinfunction "14_14") (pintype "unspecified"))
    )
    (net (code "159") (name "unconnected-(U10-Pad15)") (class "Default")
      (node (ref "U10") (pin "15") (pinfunction "15_15") (pintype "unspecified"))
    )
    (net (code "160") (name "unconnected-(U10-Pad16)") (class "Default")
      (node (ref "U10") (pin "16") (pinfunction "16_16") (pintype "unspecified"))
    )
    (net (code "161") (name "unconnected-(U10-Pad17)") (class "Default")
      (node (ref "U10") (pin "17") (pinfunction "17_17") (pintype "unspecified"))
    )
    (net (code "162") (name "unconnected-(U10-Pad18)") (class "Default")
      (node (ref "U10") (pin "18") (pinfunction "18_18") (pintype "unspecified"))
    )
    (net (code "163") (name "unconnected-(U10-Pad19)") (class "Default")
      (node (ref "U10") (pin "19") (pinfunction "19_19") (pintype "unspecified"))
    )
    (net (code "164") (name "unconnected-(U10-Pad20)") (class "Default")
      (node (ref "U10") (pin "20") (pinfunction "20_20") (pintype "unspecified"))
    )
    (net (code "165") (name "unconnected-(U10-Pad21)") (class "Default")
      (node (ref "U10") (pin "21") (pinfunction "21_21") (pintype "unspecified"))
    )
    (net (code "166") (name "unconnected-(U10-Pad22)") (class "Default")
      (node (ref "U10") (pin "22") (pinfunction "22_22") (pintype "unspecified"))
    )
    (net (code "167") (name "unconnected-(U10-Pad23)") (class "Default")
      (node (ref "U10") (pin "23") (pinfunction "23_23") (pintype "unspecified"))
    )
    (net (code "168") (name "unconnected-(U10-Pad24)") (class "Default")
      (node (ref "U10") (pin "24") (pinfunction "24_24") (pintype "unspecified"))
    )
    (net (code "169") (name "unconnected-(U10-Pad25)") (class "Default")
      (node (ref "U10") (pin "25") (pinfunction "25_25") (pintype "unspecified"))
    )
    (net (code "170") (name "unconnected-(U10-Pad26)") (class "Default")
      (node (ref "U10") (pin "26") (pinfunction "26_26") (pintype "unspecified"))
    )
    (net (code "171") (name "unconnected-(U10-Pad27)") (class "Default")
      (node (ref "U10") (pin "27") (pinfunction "27_27") (pintype "unspecified"))
    )
    (net (code "172") (name "unconnected-(U10-Pad28)") (class "Default")
      (node (ref "U10") (pin "28") (pinfunction "28_28") (pintype "unspecified"))
    )
  )
)
